# Sheet_1_MCU.net
KiCad netlist of a schematic drawn in Altium Designer
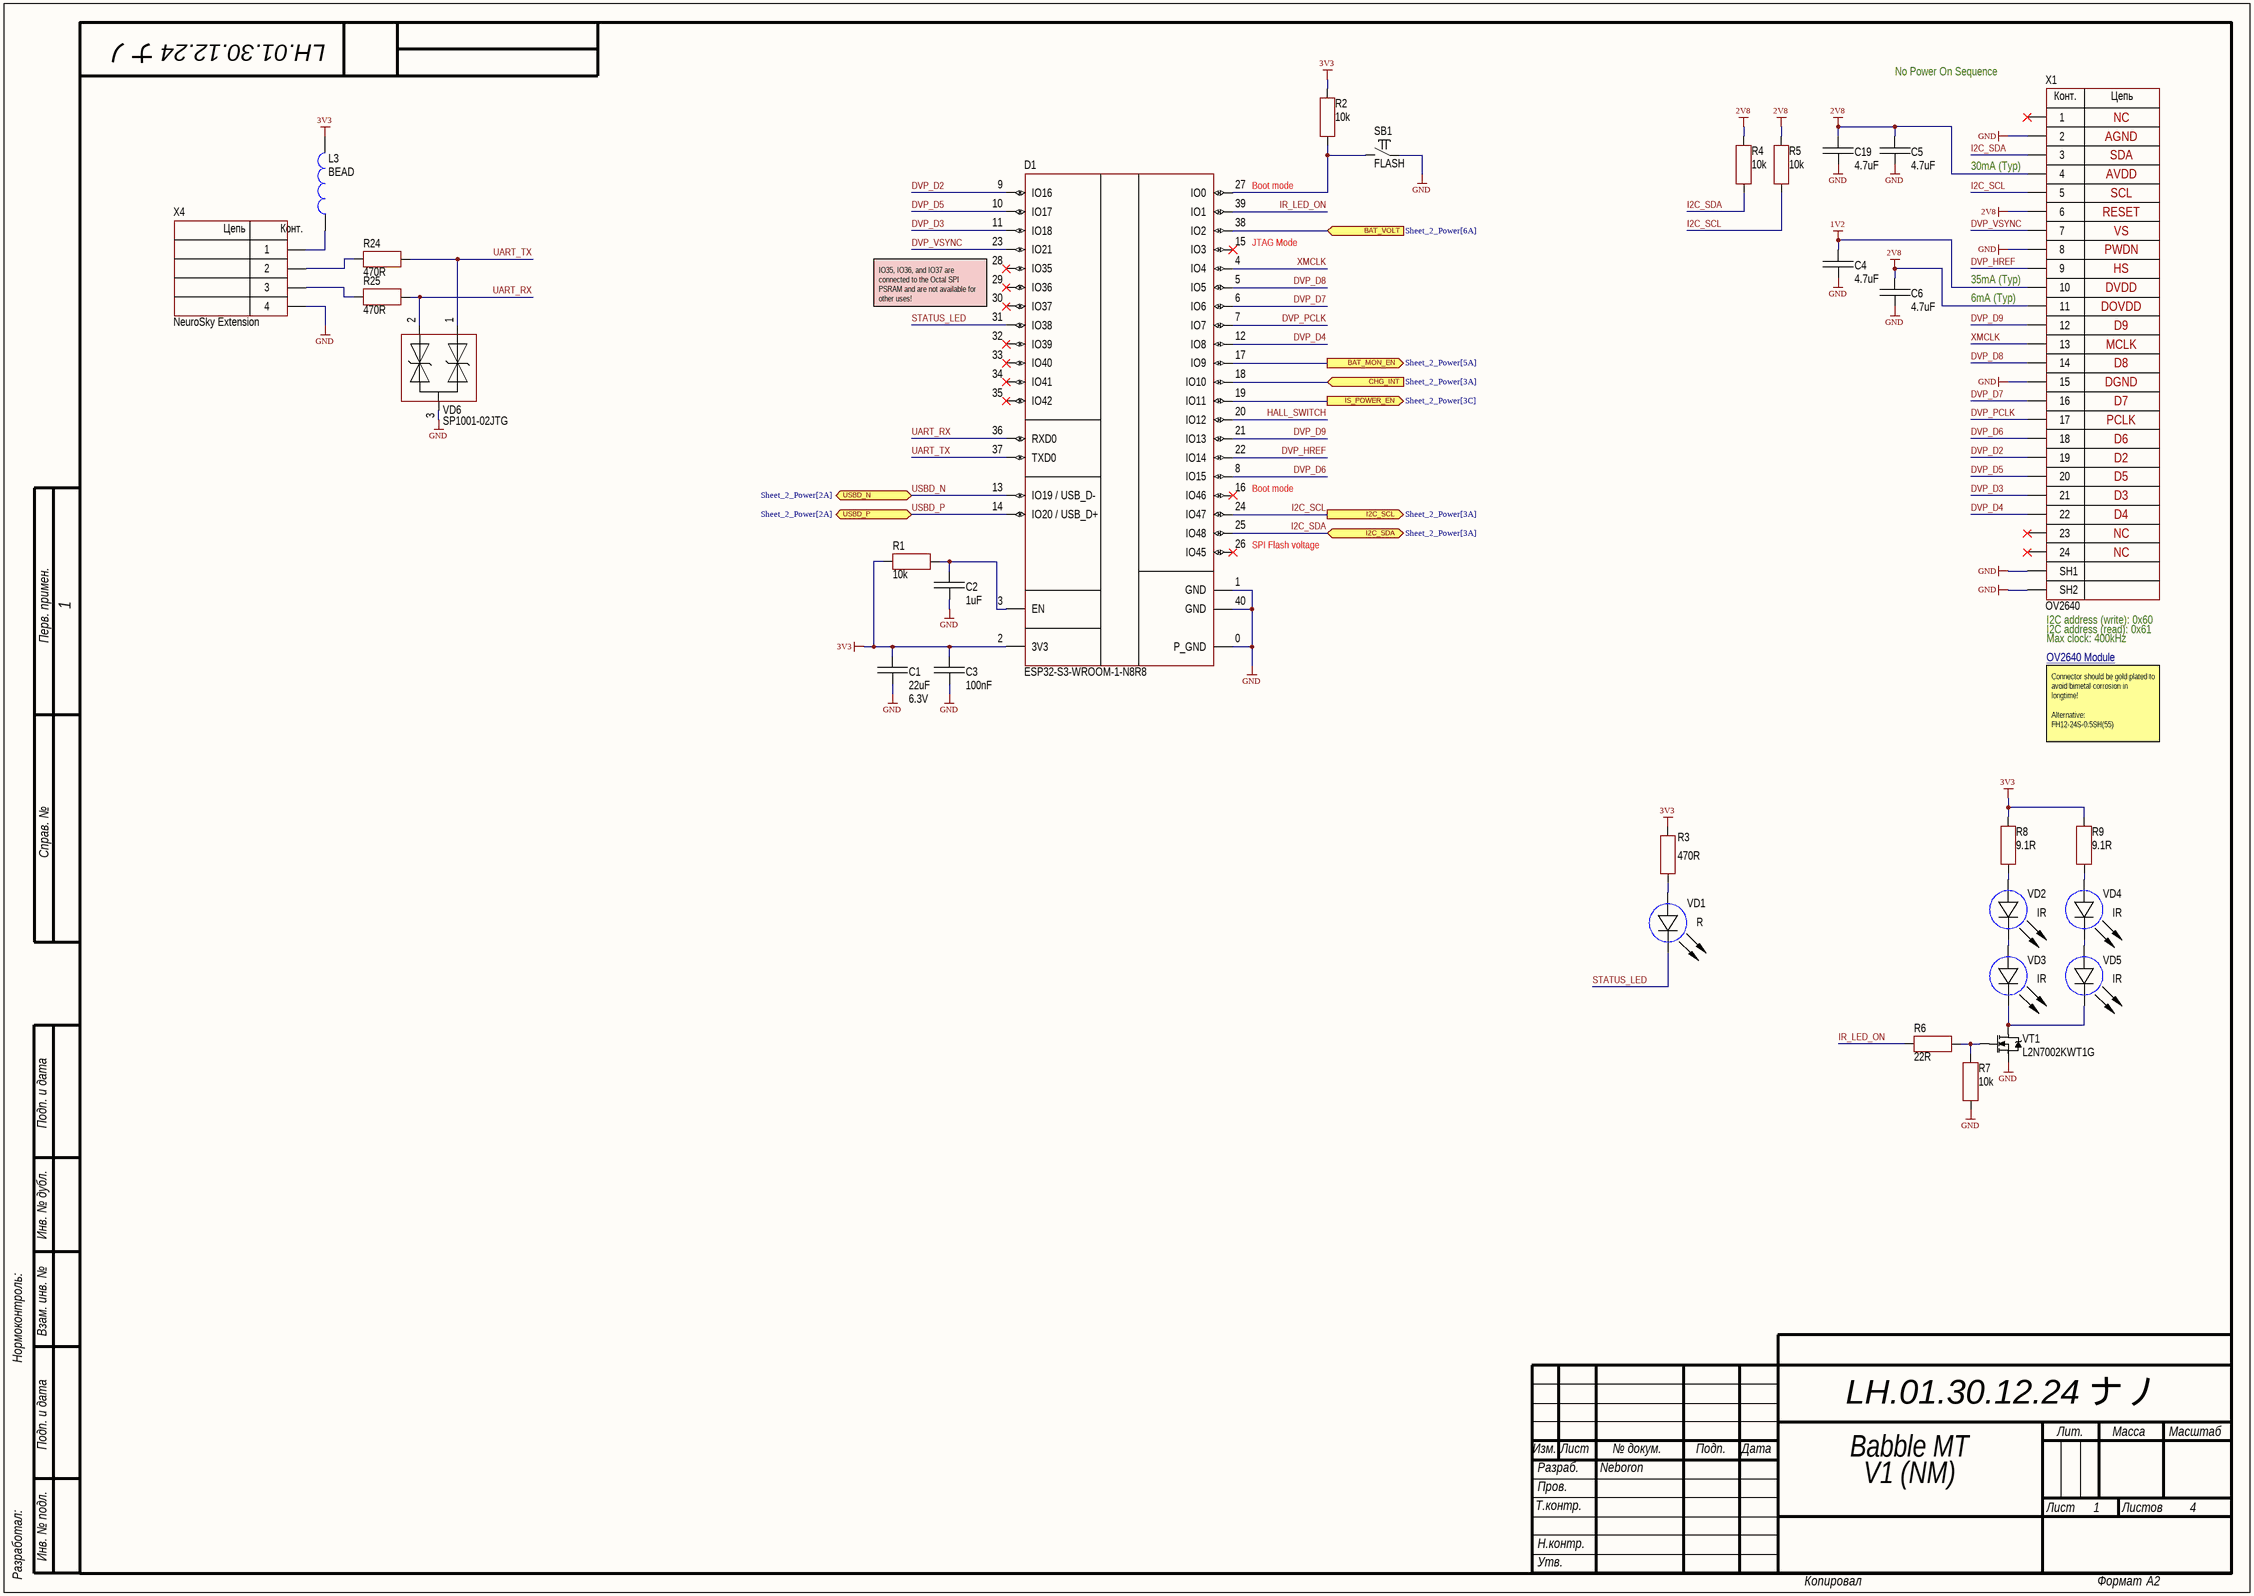
[diagram p0: Sheet_1_MCU.SchDoc]

(export (version "E")
  (design (tool "Eeschema 10.0.6"))
  (components
    (comp (ref "C1")
      (value "22uF")
      (footprint "CAP: 0603")
      (fields
        (field (name "MANUFACTURER") "Any")
        (field (name "VALUEMANUFACTURERPARTNUMBER") "Ceramic capacitor, 22uF, X5R, ±10%, 6.3V, 0603, -55...+125°C")
        (field (name "TOLERANCE") "±10%")
        (field (name "VOLTAGE") "6.3V")
      )
      (libsource (lib "capacitor") (part "Ceramic_0603"))
    )
    (comp (ref "C2")
      (value "1uF")
      (footprint "CAP: 0402")
      (fields
        (field (name "MANUFACTURER") "Any")
        (field (name "VALUEMANUFACTURERPARTNUMBER") "Ceramic capacitor, 1uF, X7R, ±10%, 6.3V, 0402, -55...+125°C")
        (field (name "TOLERANCE") "±10%")
      )
      (libsource (lib "capacitor") (part "Ceramic_0402"))
    )
    (comp (ref "C3")
      (value "100nF")
      (footprint "CAP: 0402")
      (fields
        (field (name "MANUFACTURER") "Any")
        (field (name "VALUEMANUFACTURERPARTNUMBER") "Ceramic capacitor, 100nF, X7R, ±10%, 16V, 0402, -55...+125°C")
        (field (name "TOLERANCE") "±10%")
      )
      (libsource (lib "capacitor") (part "Ceramic_0402"))
    )
    (comp (ref "C4")
      (value "4.7uF")
      (footprint "CAP: 0402")
      (fields
        (field (name "MANUFACTURER") "Any")
        (field (name "VALUEMANUFACTURERPARTNUMBER") "Ceramic capacitor, 4.7uF, X7R, ±10%, 16V, 0402, -55...+125°C")
        (field (name "TOLERANCE") "±10%")
      )
      (libsource (lib "capacitor") (part "Ceramic_0402"))
    )
    (comp (ref "C5")
      (value "4.7uF")
      (footprint "CAP: 0402")
      (fields
        (field (name "MANUFACTURER") "Any")
        (field (name "VALUEMANUFACTURERPARTNUMBER") "Ceramic capacitor, 4.7uF, X7R, ±10%, 16V, 0402, -55...+125°C")
        (field (name "TOLERANCE") "±10%")
      )
      (libsource (lib "capacitor") (part "Ceramic_0402"))
    )
    (comp (ref "C6")
      (value "4.7uF")
      (footprint "CAP: 0402")
      (fields
        (field (name "MANUFACTURER") "Any")
        (field (name "VALUEMANUFACTURERPARTNUMBER") "Ceramic capacitor, 4.7uF, X7R, ±10%, 16V, 0402, -55...+125°C")
        (field (name "TOLERANCE") "±10%")
      )
      (libsource (lib "capacitor") (part "Ceramic_0402"))
    )
    (comp (ref "C19")
      (value "4.7uF")
      (footprint "CAP: 0402")
      (fields
        (field (name "MANUFACTURER") "Any")
        (field (name "VALUEMANUFACTURERPARTNUMBER") "Ceramic capacitor, 4.7uF, X7R, ±10%, 16V, 0402, -55...+125°C")
        (field (name "TOLERANCE") "±10%")
      )
      (libsource (lib "capacitor") (part "Ceramic_0402"))
    )
    (comp (ref "D1")
      (value "~")
      (footprint "MOD: ESP32-S3-WROOM-1")
      (description "Wi-Fi")
      (fields
        (field (name "MANUFACTURER") "Espressif Systems")
        (field (name "PARTNUMBER") "ESP32-S3-WROOM-1-N8R8")
      )
      (libsource (lib "module") (part "ESP32-S3-WROOM-1-N8R8"))
    )
    (comp (ref "L3")
      (value "BEAD")
      (footprint "IND: 0402")
      (fields
        (field (name "MANUFACTURER") "Murata Electronics")
        (field (name "PARTNUMBER") "BLM15PX601SN1D")
        (field (name "VALUEMANUFACTURERPARTNUMBER") "Fixed inductor, BEAD, ±25%, 0402, 900mA, -55...+125°C")
      )
      (libsource (lib "inductor") (part "Inductor_0402"))
    )
    (comp (ref "R1")
      (value "10k")
      (footprint "RES: 0402")
      (fields
        (field (name "MANUFACTURER") "Any")
        (field (name "VALUEMANUFACTURERPARTNUMBER") "Resistor film, 10k, ±5%, 0402, 0.063W, -55...+125°C")
        (field (name "POWER") "0.063W")
      )
      (libsource (lib "resistor") (part "Resistor_0402"))
    )
    (comp (ref "R2")
      (value "10k")
      (footprint "RES: 0402")
      (fields
        (field (name "MANUFACTURER") "Any")
        (field (name "VALUEMANUFACTURERPARTNUMBER") "Resistor film, 10k, ±5%, 0402, 0.063W, -55...+125°C")
        (field (name "POWER") "0.063W")
      )
      (libsource (lib "") (part "Resistor_0402_1"))
    )
    (comp (ref "R3")
      (value "470R")
      (footprint "RES: 0402")
      (fields
        (field (name "MANUFACTURER") "Yageo")
        (field (name "PARTNUMBER") "RC0402JR-07100RL")
        (field (name "VALUEMANUFACTURERPARTNUMBER") "Resistor film, 470R, ±5%, 0402, 0.063W, -55...+125°C")
      )
      (libsource (lib "") (part "Resistor_0402_2"))
    )
    (comp (ref "R4")
      (value "10k")
      (footprint "RES: 0402")
      (fields
        (field (name "MANUFACTURER") "Any")
        (field (name "VALUEMANUFACTURERPARTNUMBER") "Resistor film, 10k, ±5%, 0402, 0.063W, -55...+125°C")
        (field (name "POWER") "0.063W")
      )
      (libsource (lib "") (part "Resistor_0402_1"))
    )
    (comp (ref "R5")
      (value "10k")
      (footprint "RES: 0402")
      (fields
        (field (name "MANUFACTURER") "Any")
        (field (name "VALUEMANUFACTURERPARTNUMBER") "Resistor film, 10k, ±5%, 0402, 0.063W, -55...+125°C")
        (field (name "POWER") "0.063W")
      )
      (libsource (lib "") (part "Resistor_0402_1"))
    )
    (comp (ref "R6")
      (value "22R")
      (footprint "RES: 0402")
      (fields
        (field (name "MANUFACTURER") "Any")
        (field (name "VALUEMANUFACTURERPARTNUMBER") "Resistor film, 22R, ±5%, 0402, 0.063W, -55...+125°C")
        (field (name "POWER") "0.063W")
      )
      (libsource (lib "resistor") (part "Resistor_0402"))
    )
    (comp (ref "R7")
      (value "10k")
      (footprint "RES: 0402")
      (fields
        (field (name "MANUFACTURER") "Any")
        (field (name "VALUEMANUFACTURERPARTNUMBER") "Resistor film, 10k, ±5%, 0402, 0.063W, -55...+125°C")
        (field (name "POWER") "0.063W")
      )
      (libsource (lib "") (part "Resistor_0402_1"))
    )
    (comp (ref "R8")
      (value "9.1R")
      (footprint "RES: 0603")
      (fields
        (field (name "MANUFACTURER") "Any")
        (field (name "VALUEMANUFACTURERPARTNUMBER") "Resistor film, 9.1R, ±5%, 0603, 0.1W, -55...+125°C")
        (field (name "POWER") "0.1W")
      )
      (libsource (lib "resistor") (part "Resistor_0603"))
    )
    (comp (ref "R9")
      (value "9.1R")
      (footprint "RES: 0603")
      (fields
        (field (name "MANUFACTURER") "Any")
        (field (name "VALUEMANUFACTURERPARTNUMBER") "Resistor film, 9.1R, ±5%, 0603, 0.1W, -55...+125°C")
        (field (name "POWER") "0.1W")
      )
      (libsource (lib "resistor") (part "Resistor_0603"))
    )
    (comp (ref "R24")
      (value "470R")
      (footprint "RES: 0402")
      (fields
        (field (name "MANUFACTURER") "Yageo")
        (field (name "PARTNUMBER") "RC0402JR-07100RL")
        (field (name "VALUEMANUFACTURERPARTNUMBER") "Resistor film, 470R, ±5%, 0402, 0.063W, -55...+125°C")
      )
      (libsource (lib "resistor") (part "Resistor_0402"))
    )
    (comp (ref "R25")
      (value "470R")
      (footprint "RES: 0402")
      (fields
        (field (name "MANUFACTURER") "Yageo")
        (field (name "PARTNUMBER") "RC0402JR-07100RL")
        (field (name "VALUEMANUFACTURERPARTNUMBER") "Resistor film, 470R, ±5%, 0402, 0.063W, -55...+125°C")
      )
      (libsource (lib "resistor") (part "Resistor_0402"))
    )
    (comp (ref "SB1")
      (value "~")
      (footprint "BUT: TS-1186F-B-A")
      (fields
        (field (name "MANUFACTURER") "XKB Connection")
        (field (name "VALUEMANUFACTURERPARTNUMBER") "Tactile button, TS-1186F")
        (field (name "PARTNUMBER") "TS-1186F-C-A")
        (field (name "COMMENTTEXT") "FLASH")
      )
      (libsource (lib "electromechanics") (part "Button_tactile"))
    )
    (comp (ref "VD1")
      (value "~")
      (footprint "LED: 0402R")
      (fields
        (field (name "VALUEMANUFACTURERPARTNUMBER") "LED, Green, *, *, *, -55...+150°C")
        (field (name "COLOR") "R")
      )
      (libsource (lib "diode") (part "LED_single"))
    )
    (comp (ref "VD2")
      (value "~")
      (footprint "LED: 1206R")
      (fields
        (field (name "MANUFACTURER") "XINGLIGHT")
        (field (name "VALUEMANUFACTURERPARTNUMBER") "LED, 850...858nm, 35mA, 1.5V, 1206, -55...+150°C")
        (field (name "PARTNUMBER") "XL-3216HIRC-850")
        (field (name "COLOR") "IR")
      )
      (libsource (lib "diode") (part "LED_single"))
    )
    (comp (ref "VD3")
      (value "~")
      (footprint "LED: 1206R")
      (fields
        (field (name "MANUFACTURER") "XINGLIGHT")
        (field (name "VALUEMANUFACTURERPARTNUMBER") "LED, 850...858nm, 35mA, 1.5V, 1206, -55...+150°C")
        (field (name "PARTNUMBER") "XL-3216HIRC-850")
        (field (name "COLOR") "IR")
      )
      (libsource (lib "diode") (part "LED_single"))
    )
    (comp (ref "VD4")
      (value "~")
      (footprint "LED: 1206R")
      (fields
        (field (name "MANUFACTURER") "XINGLIGHT")
        (field (name "VALUEMANUFACTURERPARTNUMBER") "LED, 850...858nm, 35mA, 1.5V, 1206, -55...+150°C")
        (field (name "PARTNUMBER") "XL-3216HIRC-850")
        (field (name "COLOR") "IR")
      )
      (libsource (lib "diode") (part "LED_single"))
    )
    (comp (ref "VD5")
      (value "~")
      (footprint "LED: 1206R")
      (fields
        (field (name "MANUFACTURER") "XINGLIGHT")
        (field (name "VALUEMANUFACTURERPARTNUMBER") "LED, 850...858nm, 35mA, 1.5V, 1206, -55...+150°C")
        (field (name "PARTNUMBER") "XL-3216HIRC-850")
        (field (name "COLOR") "IR")
      )
      (libsource (lib "diode") (part "LED_single"))
    )
    (comp (ref "VD6")
      (value "~")
      (footprint "SC-70")
      (fields
        (field (name "MANUFACTURER") "Littelfuse")
        (field (name "VALUEMANUFACTURERPARTNUMBER") "TVS, 5.5V, 2A, , , SC-70-3, -55...+150°C")
        (field (name "VOLTAGE") "5.5V")
        (field (name "PARTNUMBER") "SP1001-02JTG")
      )
      (libsource (lib "diode") (part "TVS_array"))
    )
    (comp (ref "VT1")
      (value "~")
      (footprint "SC-70")
      (fields
        (field (name "MANUFACTURER") "LRC")
        (field (name "VALUEMANUFACTURERPARTNUMBER") "MOSFET N-channel transistor, 60V, 380mA, , 300mW, 2.3Ohm, 34pF, SC-70, -55...+150°C")
        (field (name "PARTNUMBER") "L2N7002KWT1G")
      )
      (libsource (lib "transistor") (part "MOSFET_N_123"))
    )
    (comp (ref "X1")
      (value "~")
      (footprint "CON: FFC/FPC-24-0.5(Hirose)")
      (fields
        (field (name "MANUFACTURER") "Hirose")
        (field (name "VALUEMANUFACTURERPARTNUMBER") "Connector, 24pin, 0.5mm, FFC/FPC, 0.5A")
        (field (name "PARTNUMBER") "TF31-24S-0.5SH(800)")
        (field (name "COMMENTTEXT") "OV2640")
      )
      (libsource (lib "connector") (part "Connector_FFC_24 (TF31-24S-0.5SH(800))"))
    )
    (comp (ref "X4")
      (value "~")
      (footprint "CON: SM04B-GHS")
      (fields
        (field (name "MANUFACTURER") "JST")
        (field (name "VALUEMANUFACTURERPARTNUMBER") "Connector, 4pin, 1.25mm, 50VDC, 1A")
        (field (name "PARTNUMBER") "SM04B-GHS")
        (field (name "COMMENTTEXT") "NeuroSky Extension")
      )
      (libsource (lib "connector") (part "Connector_SM04B"))
    )
  )
  (nets
    (net (code "1") (name "/BAT_MON_EN") (class "Default")
      (node (ref "D1") (pin "17") (pinfunction "IO9_17") (pintype "bidirectional"))
    )
    (net (code "2") (name "/BAT_VOLT") (class "Default")
      (node (ref "D1") (pin "38") (pinfunction "IO2_38") (pintype "bidirectional"))
    )
    (net (code "3") (name "/CHG_INT") (class "Default")
      (node (ref "D1") (pin "18") (pinfunction "IO10_18") (pintype "bidirectional"))
    )
    (net (code "4") (name "/DVP_D2") (class "Default")
      (node (ref "D1") (pin "9") (pinfunction "IO16_9") (pintype "bidirectional"))
      (node (ref "X1") (pin "19") (pinfunction "19_19") (pintype "passive"))
    )
    (net (code "5") (name "/DVP_D3") (class "Default")
      (node (ref "D1") (pin "11") (pinfunction "IO18_11") (pintype "bidirectional"))
      (node (ref "X1") (pin "21") (pinfunction "21_21") (pintype "passive"))
    )
    (net (code "6") (name "/DVP_D4") (class "Default")
      (node (ref "D1") (pin "12") (pinfunction "IO8_12") (pintype "bidirectional"))
      (node (ref "X1") (pin "22") (pinfunction "22_22") (pintype "passive"))
    )
    (net (code "7") (name "/DVP_D5") (class "Default")
      (node (ref "D1") (pin "10") (pinfunction "IO17_10") (pintype "bidirectional"))
      (node (ref "X1") (pin "20") (pinfunction "20_20") (pintype "passive"))
    )
    (net (code "8") (name "/DVP_D6") (class "Default")
      (node (ref "D1") (pin "8") (pinfunction "IO15_8") (pintype "bidirectional"))
      (node (ref "X1") (pin "18") (pinfunction "18_18") (pintype "passive"))
    )
    (net (code "9") (name "/DVP_D7") (class "Default")
      (node (ref "D1") (pin "6") (pinfunction "IO6_6") (pintype "bidirectional"))
      (node (ref "X1") (pin "16") (pinfunction "16_16") (pintype "passive"))
    )
    (net (code "10") (name "/DVP_D8") (class "Default")
      (node (ref "D1") (pin "5") (pinfunction "IO5_5") (pintype "bidirectional"))
      (node (ref "X1") (pin "14") (pinfunction "14_14") (pintype "passive"))
    )
    (net (code "11") (name "/DVP_D9") (class "Default")
      (node (ref "D1") (pin "21") (pinfunction "IO13_21") (pintype "bidirectional"))
      (node (ref "X1") (pin "12") (pinfunction "12_12") (pintype "passive"))
    )
    (net (code "12") (name "/DVP_HREF") (class "Default")
      (node (ref "D1") (pin "22") (pinfunction "IO14_22") (pintype "bidirectional"))
      (node (ref "X1") (pin "9") (pinfunction "9_9") (pintype "passive"))
    )
    (net (code "13") (name "/DVP_PCLK") (class "Default")
      (node (ref "D1") (pin "7") (pinfunction "IO7_7") (pintype "bidirectional"))
      (node (ref "X1") (pin "17") (pinfunction "17_17") (pintype "passive"))
    )
    (net (code "14") (name "/DVP_VSYNC") (class "Default")
      (node (ref "D1") (pin "23") (pinfunction "IO21_23") (pintype "bidirectional"))
      (node (ref "X1") (pin "7") (pinfunction "7_7") (pintype "passive"))
    )
    (net (code "15") (name "/HALL_SWITCH") (class "Default")
      (node (ref "D1") (pin "20") (pinfunction "IO12_20") (pintype "bidirectional"))
    )
    (net (code "16") (name "/I2C_SCL") (class "Default")
      (node (ref "D1") (pin "24") (pinfunction "IO47_24") (pintype "bidirectional"))
      (node (ref "R5") (pin "2") (pinfunction "2_2") (pintype "passive"))
      (node (ref "X1") (pin "5") (pinfunction "5_5") (pintype "passive"))
    )
    (net (code "17") (name "/I2C_SDA") (class "Default")
      (node (ref "D1") (pin "25") (pinfunction "IO48_25") (pintype "bidirectional"))
      (node (ref "R4") (pin "2") (pinfunction "2_2") (pintype "passive"))
      (node (ref "X1") (pin "3") (pinfunction "3_3") (pintype "passive"))
    )
    (net (code "18") (name "/IR_LED_ON") (class "Default")
      (node (ref "D1") (pin "39") (pinfunction "IO1_39") (pintype "bidirectional"))
      (node (ref "R6") (pin "2") (pinfunction "2_2") (pintype "passive"))
    )
    (net (code "19") (name "/IS_POWER_EN") (class "Default")
      (node (ref "D1") (pin "19") (pinfunction "IO11_19") (pintype "bidirectional"))
    )
    (net (code "20") (name "/STATUS_LED") (class "Default")
      (node (ref "D1") (pin "31") (pinfunction "IO38_31") (pintype "bidirectional"))
      (node (ref "VD1") (pin "1") (pinfunction "C_1") (pintype "passive"))
    )
    (net (code "21") (name "/UART_RX") (class "Default")
      (node (ref "D1") (pin "36") (pinfunction "RXD0_36") (pintype "bidirectional"))
      (node (ref "R25") (pin "1") (pinfunction "1_1") (pintype "passive"))
      (node (ref "VD6") (pin "2") (pintype "passive"))
    )
    (net (code "22") (name "/UART_TX") (class "Default")
      (node (ref "D1") (pin "37") (pinfunction "TXD0_37") (pintype "bidirectional"))
      (node (ref "R24") (pin "1") (pinfunction "1_1") (pintype "passive"))
      (node (ref "VD6") (pin "1") (pintype "passive"))
    )
    (net (code "23") (name "/USBD_N") (class "Default")
      (node (ref "D1") (pin "13") (pinfunction "IO19_/_USB_D-_13") (pintype "bidirectional"))
    )
    (net (code "24") (name "/USBD_P") (class "Default")
      (node (ref "D1") (pin "14") (pinfunction "IO20_/_USB_D+_14") (pintype "bidirectional"))
    )
    (net (code "25") (name "/XMCLK") (class "Default")
      (node (ref "D1") (pin "4") (pinfunction "IO4_4") (pintype "bidirectional"))
      (node (ref "X1") (pin "13") (pinfunction "13_13") (pintype "passive"))
    )
    (net (code "26") (name "1V2") (class "Default")
      (node (ref "C4") (pin "1") (pinfunction "1_1") (pintype "passive"))
      (node (ref "X1") (pin "10") (pinfunction "10_10") (pintype "passive"))
    )
    (net (code "27") (name "2V8") (class "Default")
      (node (ref "C19") (pin "1") (pinfunction "1_1") (pintype "passive"))
      (node (ref "C5") (pin "1") (pinfunction "1_1") (pintype "passive"))
      (node (ref "C6") (pin "1") (pinfunction "1_1") (pintype "passive"))
      (node (ref "R4") (pin "1") (pinfunction "1_1") (pintype "passive"))
      (node (ref "R5") (pin "1") (pinfunction "1_1") (pintype "passive"))
      (node (ref "X1") (pin "11") (pinfunction "11_11") (pintype "passive"))
      (node (ref "X1") (pin "4") (pinfunction "4_4") (pintype "passive"))
      (node (ref "X1") (pin "6") (pinfunction "6_6") (pintype "passive"))
    )
    (net (code "28") (name "3V3") (class "Default")
      (node (ref "C1") (pin "2") (pinfunction "2_2") (pintype "passive"))
      (node (ref "C3") (pin "2") (pinfunction "2_2") (pintype "passive"))
      (node (ref "D1") (pin "2") (pinfunction "3V3_2") (pintype "power_in"))
      (node (ref "L3") (pin "1") (pinfunction "1_1") (pintype "passive"))
      (node (ref "R1") (pin "2") (pinfunction "2_2") (pintype "passive"))
      (node (ref "R2") (pin "1") (pinfunction "1_1") (pintype "passive"))
      (node (ref "R3") (pin "2") (pinfunction "2_2") (pintype "passive"))
      (node (ref "R8") (pin "2") (pinfunction "2_2") (pintype "passive"))
      (node (ref "R9") (pin "2") (pinfunction "2_2") (pintype "passive"))
    )
    (net (code "29") (name "GND") (class "Default")
      (node (ref "C1") (pin "1") (pinfunction "1_1") (pintype "passive"))
      (node (ref "C19") (pin "2") (pinfunction "2_2") (pintype "passive"))
      (node (ref "C2") (pin "1") (pinfunction "1_1") (pintype "passive"))
      (node (ref "C3") (pin "1") (pinfunction "1_1") (pintype "passive"))
      (node (ref "C4") (pin "2") (pinfunction "2_2") (pintype "passive"))
      (node (ref "C5") (pin "2") (pinfunction "2_2") (pintype "passive"))
      (node (ref "C6") (pin "2") (pinfunction "2_2") (pintype "passive"))
      (node (ref "D1") (pin "0") (pinfunction "P_GND_0") (pintype "power_in"))
      (node (ref "D1") (pin "1") (pinfunction "GND_1") (pintype "power_in"))
      (node (ref "D1") (pin "40") (pinfunction "GND_40") (pintype "power_in"))
      (node (ref "R7") (pin "2") (pinfunction "2_2") (pintype "passive"))
      (node (ref "SB1") (pin "1") (pinfunction "1_1") (pintype "passive"))
      (node (ref "VD6") (pin "3") (pintype "passive"))
      (node (ref "VT1") (pin "3") (pinfunction "S_3") (pintype "passive"))
      (node (ref "X1") (pin "15") (pinfunction "15_15") (pintype "passive"))
      (node (ref "X1") (pin "2") (pinfunction "2_2") (pintype "passive"))
      (node (ref "X1") (pin "8") (pinfunction "8_8") (pintype "passive"))
      (node (ref "X1") (pin "SH1") (pinfunction "SH1_SH1") (pintype "passive"))
      (node (ref "X1") (pin "SH2") (pinfunction "SH2_SH2") (pintype "passive"))
      (node (ref "X4") (pin "4") (pinfunction "4_4") (pintype "power_in"))
    )
    (net (code "30") (name "Net-(D1-EN)") (class "Default")
      (node (ref "C2") (pin "2") (pinfunction "2_2") (pintype "passive"))
      (node (ref "D1") (pin "3") (pinfunction "EN_3") (pintype "passive"))
      (node (ref "R1") (pin "1") (pinfunction "1_1") (pintype "passive"))
    )
    (net (code "31") (name "Net-(D1-IO0)") (class "Default")
      (node (ref "D1") (pin "27") (pinfunction "IO0_27") (pintype "bidirectional"))
      (node (ref "R2") (pin "2") (pinfunction "2_2") (pintype "passive"))
      (node (ref "SB1") (pin "2") (pinfunction "2_2") (pintype "passive"))
    )
    (net (code "32") (name "Net-(L3-Pad2)") (class "Default")
      (node (ref "L3") (pin "2") (pinfunction "2_2") (pintype "passive"))
      (node (ref "X4") (pin "1") (pinfunction "1_1") (pintype "passive"))
    )
    (net (code "33") (name "Net-(R24-Pad2)") (class "Default")
      (node (ref "R24") (pin "2") (pinfunction "2_2") (pintype "passive"))
      (node (ref "X4") (pin "2") (pinfunction "2_2") (pintype "passive"))
    )
    (net (code "34") (name "Net-(R25-Pad2)") (class "Default")
      (node (ref "R25") (pin "2") (pinfunction "2_2") (pintype "passive"))
      (node (ref "X4") (pin "3") (pinfunction "3_3") (pintype "power_in"))
    )
    (net (code "35") (name "Net-(VD1-A)") (class "Default")
      (node (ref "R3") (pin "1") (pinfunction "1_1") (pintype "passive"))
      (node (ref "VD1") (pin "2") (pinfunction "A_2") (pintype "passive"))
    )
    (net (code "36") (name "Net-(VD2-A)") (class "Default")
      (node (ref "R8") (pin "1") (pinfunction "1_1") (pintype "passive"))
      (node (ref "VD2") (pin "2") (pinfunction "A_2") (pintype "passive"))
    )
    (net (code "37") (name "Net-(VD2-C)") (class "Default")
      (node (ref "VD2") (pin "1") (pinfunction "C_1") (pintype "passive"))
      (node (ref "VD3") (pin "2") (pinfunction "A_2") (pintype "passive"))
    )
    (net (code "38") (name "Net-(VD3-C)") (class "Default")
      (node (ref "VD3") (pin "1") (pinfunction "C_1") (pintype "passive"))
      (node (ref "VD5") (pin "1") (pinfunction "C_1") (pintype "passive"))
      (node (ref "VT1") (pin "2") (pinfunction "D_2") (pintype "passive"))
    )
    (net (code "39") (name "Net-(VD4-A)") (class "Default")
      (node (ref "R9") (pin "1") (pinfunction "1_1") (pintype "passive"))
      (node (ref "VD4") (pin "2") (pinfunction "A_2") (pintype "passive"))
    )
    (net (code "40") (name "Net-(VD4-C)") (class "Default")
      (node (ref "VD4") (pin "1") (pinfunction "C_1") (pintype "passive"))
      (node (ref "VD5") (pin "2") (pinfunction "A_2") (pintype "passive"))
    )
    (net (code "41") (name "Net-(VT1-G)") (class "Default")
      (node (ref "R6") (pin "1") (pinfunction "1_1") (pintype "passive"))
      (node (ref "R7") (pin "1") (pinfunction "1_1") (pintype "passive"))
      (node (ref "VT1") (pin "1") (pinfunction "G_1") (pintype "passive"))
    )
    (net (code "42") (name "unconnected-(D1-IO3-Pad15)") (class "Default")
      (node (ref "D1") (pin "15") (pinfunction "IO3_15") (pintype "bidirectional+no_connect"))
    )
    (net (code "43") (name "unconnected-(D1-IO35-Pad28)") (class "Default")
      (node (ref "D1") (pin "28") (pinfunction "IO35_28") (pintype "bidirectional+no_connect"))
    )
    (net (code "44") (name "unconnected-(D1-IO36-Pad29)") (class "Default")
      (node (ref "D1") (pin "29") (pinfunction "IO36_29") (pintype "bidirectional+no_connect"))
    )
    (net (code "45") (name "unconnected-(D1-IO37-Pad30)") (class "Default")
      (node (ref "D1") (pin "30") (pinfunction "IO37_30") (pintype "bidirectional+no_connect"))
    )
    (net (code "46") (name "unconnected-(D1-IO39-Pad32)") (class "Default")
      (node (ref "D1") (pin "32") (pinfunction "IO39_32") (pintype "bidirectional+no_connect"))
    )
    (net (code "47") (name "unconnected-(D1-IO40-Pad33)") (class "Default")
      (node (ref "D1") (pin "33") (pinfunction "IO40_33") (pintype "bidirectional+no_connect"))
    )
    (net (code "48") (name "unconnected-(D1-IO41-Pad34)") (class "Default")
      (node (ref "D1") (pin "34") (pinfunction "IO41_34") (pintype "bidirectional+no_connect"))
    )
    (net (code "49") (name "unconnected-(D1-IO42-Pad35)") (class "Default")
      (node (ref "D1") (pin "35") (pinfunction "IO42_35") (pintype "bidirectional+no_connect"))
    )
    (net (code "50") (name "unconnected-(D1-IO45-Pad26)") (class "Default")
      (node (ref "D1") (pin "26") (pinfunction "IO45_26") (pintype "bidirectional+no_connect"))
    )
    (net (code "51") (name "unconnected-(D1-IO46-Pad16)") (class "Default")
      (node (ref "D1") (pin "16") (pinfunction "IO46_16") (pintype "bidirectional+no_connect"))
    )
    (net (code "52") (name "unconnected-(X1-Pad1)") (class "Default")
      (node (ref "X1") (pin "1") (pinfunction "1_1") (pintype "passive+no_connect"))
    )
    (net (code "53") (name "unconnected-(X1-Pad23)") (class "Default")
      (node (ref "X1") (pin "23") (pinfunction "23_23") (pintype "passive+no_connect"))
    )
    (net (code "54") (name "unconnected-(X1-Pad24)") (class "Default")
      (node (ref "X1") (pin "24") (pinfunction "24_24") (pintype "passive+no_connect"))
    )
  )
)
